# pc.net
KiCad netlist of a schematic drawn in EAGLE
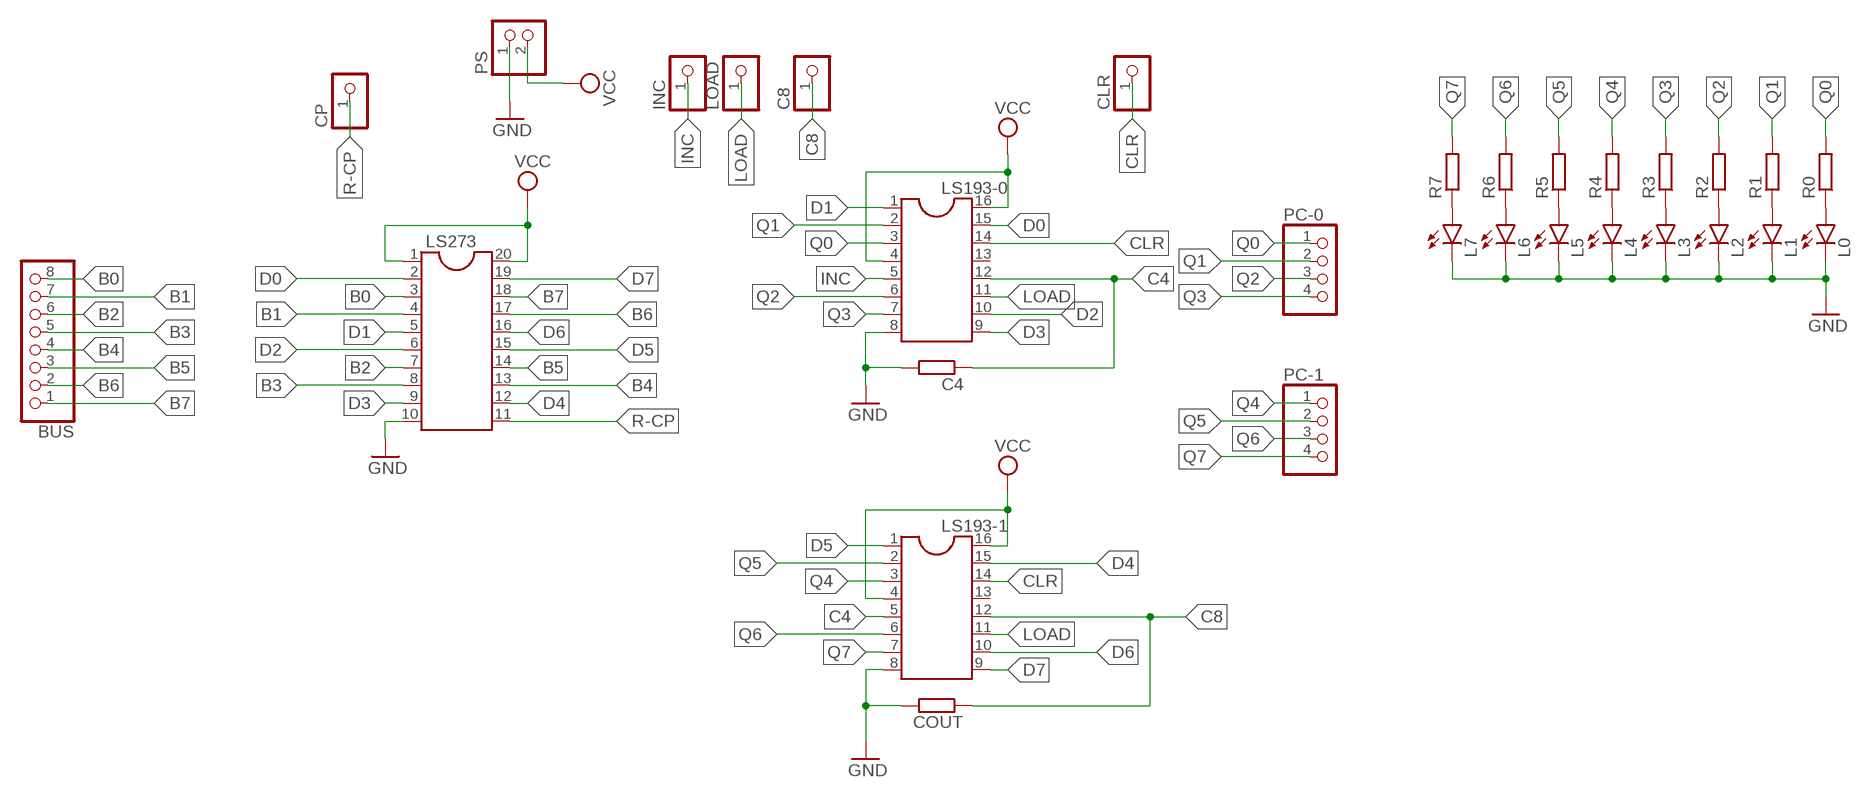
[diagram p0: schematic, sheet 1]

(export (version "E")
  (design (tool "Eeschema 10.0.6"))
  (components
    (comp (ref "BUS")
      (value "PINHD-1X8")
      (footprint "eagle-import:1X08")
      (libsource (lib "eagle-import") (part "PINHD-1X8"))
    )
    (comp (ref "C4")
      (value "R-EU_0204/7")
      (footprint "eagle-import:0204_7")
      (libsource (lib "eagle-import") (part "R-EU_0204/7"))
    )
    (comp (ref "C8")
      (value "PINHD-1X1")
      (footprint "eagle-import:1X01")
      (libsource (lib "eagle-import") (part "PINHD-1X1"))
    )
    (comp (ref "CLR")
      (value "PINHD-1X1")
      (footprint "eagle-import:1X01")
      (libsource (lib "eagle-import") (part "PINHD-1X1"))
    )
    (comp (ref "COUT")
      (value "R-EU_0204/7")
      (footprint "eagle-import:0204_7")
      (libsource (lib "eagle-import") (part "R-EU_0204/7"))
    )
    (comp (ref "CP")
      (value "PINHD-1X1")
      (footprint "eagle-import:1X01")
      (libsource (lib "eagle-import") (part "PINHD-1X1"))
    )
    (comp (ref "INC")
      (value "PINHD-1X1")
      (footprint "eagle-import:1X01")
      (libsource (lib "eagle-import") (part "PINHD-1X1"))
    )
    (comp (ref "L0")
      (value "LED5MM")
      (footprint "eagle-import:LED5MM")
      (libsource (lib "eagle-import") (part "LED5MM"))
    )
    (comp (ref "L1")
      (value "LED5MM")
      (footprint "eagle-import:LED5MM")
      (libsource (lib "eagle-import") (part "LED5MM"))
    )
    (comp (ref "L2")
      (value "LED5MM")
      (footprint "eagle-import:LED5MM")
      (libsource (lib "eagle-import") (part "LED5MM"))
    )
    (comp (ref "L3")
      (value "LED5MM")
      (footprint "eagle-import:LED5MM")
      (libsource (lib "eagle-import") (part "LED5MM"))
    )
    (comp (ref "L4")
      (value "LED5MM")
      (footprint "eagle-import:LED5MM")
      (libsource (lib "eagle-import") (part "LED5MM"))
    )
    (comp (ref "L5")
      (value "LED5MM")
      (footprint "eagle-import:LED5MM")
      (libsource (lib "eagle-import") (part "LED5MM"))
    )
    (comp (ref "L6")
      (value "LED5MM")
      (footprint "eagle-import:LED5MM")
      (libsource (lib "eagle-import") (part "LED5MM"))
    )
    (comp (ref "L7")
      (value "LED5MM")
      (footprint "eagle-import:LED5MM")
      (libsource (lib "eagle-import") (part "LED5MM"))
    )
    (comp (ref "LOAD")
      (value "PINHD-1X1")
      (footprint "eagle-import:1X01")
      (libsource (lib "eagle-import") (part "PINHD-1X1"))
    )
    (comp (ref "LS193-0")
      (value "DIL16S")
      (footprint "eagle-import:SOCKET-16")
      (libsource (lib "eagle-import") (part "DIL16S"))
    )
    (comp (ref "LS193-1")
      (value "DIL16S")
      (footprint "eagle-import:SOCKET-16")
      (libsource (lib "eagle-import") (part "DIL16S"))
    )
    (comp (ref "LS273")
      (value "DIL20S")
      (footprint "eagle-import:SOCKET-20")
      (libsource (lib "eagle-import") (part "DIL20S"))
    )
    (comp (ref "PC-0")
      (value "PINHD-1X4")
      (footprint "eagle-import:1X04")
      (libsource (lib "eagle-import") (part "PINHD-1X4"))
    )
    (comp (ref "PC-1")
      (value "PINHD-1X4")
      (footprint "eagle-import:1X04")
      (libsource (lib "eagle-import") (part "PINHD-1X4"))
    )
    (comp (ref "PS")
      (value "PINHD-1X2")
      (footprint "eagle-import:1X02")
      (libsource (lib "eagle-import") (part "PINHD-1X2"))
    )
    (comp (ref "R0")
      (value "R-EU_0204/7")
      (footprint "eagle-import:0204_7")
      (libsource (lib "eagle-import") (part "R-EU_0204/7"))
    )
    (comp (ref "R1")
      (value "R-EU_0204/7")
      (footprint "eagle-import:0204_7")
      (libsource (lib "eagle-import") (part "R-EU_0204/7"))
    )
    (comp (ref "R2")
      (value "R-EU_0204/7")
      (footprint "eagle-import:0204_7")
      (libsource (lib "eagle-import") (part "R-EU_0204/7"))
    )
    (comp (ref "R3")
      (value "R-EU_0204/7")
      (footprint "eagle-import:0204_7")
      (libsource (lib "eagle-import") (part "R-EU_0204/7"))
    )
    (comp (ref "R4")
      (value "R-EU_0204/7")
      (footprint "eagle-import:0204_7")
      (libsource (lib "eagle-import") (part "R-EU_0204/7"))
    )
    (comp (ref "R5")
      (value "R-EU_0204/7")
      (footprint "eagle-import:0204_7")
      (libsource (lib "eagle-import") (part "R-EU_0204/7"))
    )
    (comp (ref "R6")
      (value "R-EU_0204/7")
      (footprint "eagle-import:0204_7")
      (libsource (lib "eagle-import") (part "R-EU_0204/7"))
    )
    (comp (ref "R7")
      (value "R-EU_0204/7")
      (footprint "eagle-import:0204_7")
      (libsource (lib "eagle-import") (part "R-EU_0204/7"))
    )
  )
  (nets
    (net (code "1") (name "B0") (class "Default")
      (node (ref "BUS") (pin "8") (pinfunction "8_8") (pintype "passive"))
      (node (ref "LS273") (pin "3") (pinfunction "3_3") (pintype "passive"))
    )
    (net (code "2") (name "B1") (class "Default")
      (node (ref "BUS") (pin "7") (pinfunction "7_7") (pintype "passive"))
      (node (ref "LS273") (pin "4") (pinfunction "4_4") (pintype "passive"))
    )
    (net (code "3") (name "B2") (class "Default")
      (node (ref "BUS") (pin "6") (pinfunction "6_6") (pintype "passive"))
      (node (ref "LS273") (pin "7") (pinfunction "7_7") (pintype "passive"))
    )
    (net (code "4") (name "B3") (class "Default")
      (node (ref "BUS") (pin "5") (pinfunction "5_5") (pintype "passive"))
      (node (ref "LS273") (pin "8") (pinfunction "8_8") (pintype "passive"))
    )
    (net (code "5") (name "B4") (class "Default")
      (node (ref "BUS") (pin "4") (pinfunction "4_4") (pintype "passive"))
      (node (ref "LS273") (pin "13") (pinfunction "13_13") (pintype "passive"))
    )
    (net (code "6") (name "B5") (class "Default")
      (node (ref "BUS") (pin "3") (pinfunction "3_3") (pintype "passive"))
      (node (ref "LS273") (pin "14") (pinfunction "14_14") (pintype "passive"))
    )
    (net (code "7") (name "B6") (class "Default")
      (node (ref "BUS") (pin "2") (pinfunction "2_2") (pintype "passive"))
      (node (ref "LS273") (pin "17") (pinfunction "17_17") (pintype "passive"))
    )
    (net (code "8") (name "B7") (class "Default")
      (node (ref "BUS") (pin "1") (pinfunction "1_1") (pintype "passive"))
      (node (ref "LS273") (pin "18") (pinfunction "18_18") (pintype "passive"))
    )
    (net (code "9") (name "C4") (class "Default")
      (node (ref "C4") (pin "1") (pinfunction "1_1") (pintype "passive"))
      (node (ref "LS193-0") (pin "12") (pinfunction "12_12") (pintype "passive"))
      (node (ref "LS193-1") (pin "5") (pinfunction "5_5") (pintype "passive"))
    )
    (net (code "10") (name "C8") (class "Default")
      (node (ref "C8") (pin "1") (pinfunction "1_1") (pintype "passive"))
      (node (ref "COUT") (pin "1") (pinfunction "1_1") (pintype "passive"))
      (node (ref "LS193-1") (pin "12") (pinfunction "12_12") (pintype "passive"))
    )
    (net (code "11") (name "CLR") (class "Default")
      (node (ref "CLR") (pin "1") (pinfunction "1_1") (pintype "passive"))
      (node (ref "LS193-0") (pin "14") (pinfunction "14_14") (pintype "passive"))
      (node (ref "LS193-1") (pin "14") (pinfunction "14_14") (pintype "passive"))
    )
    (net (code "12") (name "D0") (class "Default")
      (node (ref "LS193-0") (pin "15") (pinfunction "15_15") (pintype "passive"))
      (node (ref "LS273") (pin "2") (pinfunction "2_2") (pintype "passive"))
    )
    (net (code "13") (name "D1") (class "Default")
      (node (ref "LS193-0") (pin "1") (pinfunction "1_1") (pintype "passive"))
      (node (ref "LS273") (pin "5") (pinfunction "5_5") (pintype "passive"))
    )
    (net (code "14") (name "D2") (class "Default")
      (node (ref "LS193-0") (pin "10") (pinfunction "10_10") (pintype "passive"))
      (node (ref "LS273") (pin "6") (pinfunction "6_6") (pintype "passive"))
    )
    (net (code "15") (name "D3") (class "Default")
      (node (ref "LS193-0") (pin "9") (pinfunction "9_9") (pintype "passive"))
      (node (ref "LS273") (pin "9") (pinfunction "9_9") (pintype "passive"))
    )
    (net (code "16") (name "D4") (class "Default")
      (node (ref "LS193-1") (pin "15") (pinfunction "15_15") (pintype "passive"))
      (node (ref "LS273") (pin "12") (pinfunction "12_12") (pintype "passive"))
    )
    (net (code "17") (name "D5") (class "Default")
      (node (ref "LS193-1") (pin "1") (pinfunction "1_1") (pintype "passive"))
      (node (ref "LS273") (pin "15") (pinfunction "15_15") (pintype "passive"))
    )
    (net (code "18") (name "D6") (class "Default")
      (node (ref "LS193-1") (pin "10") (pinfunction "10_10") (pintype "passive"))
      (node (ref "LS273") (pin "16") (pinfunction "16_16") (pintype "passive"))
    )
    (net (code "19") (name "D7") (class "Default")
      (node (ref "LS193-1") (pin "9") (pinfunction "9_9") (pintype "passive"))
      (node (ref "LS273") (pin "19") (pinfunction "19_19") (pintype "passive"))
    )
    (net (code "20") (name "GND") (class "Default")
      (node (ref "C4") (pin "2") (pinfunction "2_2") (pintype "passive"))
      (node (ref "COUT") (pin "2") (pinfunction "2_2") (pintype "passive"))
      (node (ref "L0") (pin "K") (pinfunction "C_K") (pintype "passive"))
      (node (ref "L1") (pin "K") (pinfunction "C_K") (pintype "passive"))
      (node (ref "L2") (pin "K") (pinfunction "C_K") (pintype "passive"))
      (node (ref "L3") (pin "K") (pinfunction "C_K") (pintype "passive"))
      (node (ref "L4") (pin "K") (pinfunction "C_K") (pintype "passive"))
      (node (ref "L5") (pin "K") (pinfunction "C_K") (pintype "passive"))
      (node (ref "L6") (pin "K") (pinfunction "C_K") (pintype "passive"))
      (node (ref "L7") (pin "K") (pinfunction "C_K") (pintype "passive"))
      (node (ref "LS193-0") (pin "8") (pinfunction "8_8") (pintype "passive"))
      (node (ref "LS193-1") (pin "8") (pinfunction "8_8") (pintype "passive"))
      (node (ref "LS273") (pin "10") (pinfunction "10_10") (pintype "passive"))
      (node (ref "PS") (pin "1") (pinfunction "1_1") (pintype "passive"))
    )
    (net (code "21") (name "INC") (class "Default")
      (node (ref "INC") (pin "1") (pinfunction "1_1") (pintype "passive"))
      (node (ref "LS193-0") (pin "5") (pinfunction "5_5") (pintype "passive"))
    )
    (net (code "22") (name "LOAD") (class "Default")
      (node (ref "LOAD") (pin "1") (pinfunction "1_1") (pintype "passive"))
      (node (ref "LS193-0") (pin "11") (pinfunction "11_11") (pintype "passive"))
      (node (ref "LS193-1") (pin "11") (pinfunction "11_11") (pintype "passive"))
    )
    (net (code "23") (name "Net-(L0-PadA)") (class "Default")
      (node (ref "L0") (pin "A") (pinfunction "A_A") (pintype "passive"))
      (node (ref "R0") (pin "1") (pinfunction "1_1") (pintype "passive"))
    )
    (net (code "24") (name "Net-(L1-PadA)") (class "Default")
      (node (ref "L1") (pin "A") (pinfunction "A_A") (pintype "passive"))
      (node (ref "R1") (pin "1") (pinfunction "1_1") (pintype "passive"))
    )
    (net (code "25") (name "Net-(L2-PadA)") (class "Default")
      (node (ref "L2") (pin "A") (pinfunction "A_A") (pintype "passive"))
      (node (ref "R2") (pin "1") (pinfunction "1_1") (pintype "passive"))
    )
    (net (code "26") (name "Net-(L3-PadA)") (class "Default")
      (node (ref "L3") (pin "A") (pinfunction "A_A") (pintype "passive"))
      (node (ref "R3") (pin "1") (pinfunction "1_1") (pintype "passive"))
    )
    (net (code "27") (name "Net-(L4-PadA)") (class "Default")
      (node (ref "L4") (pin "A") (pinfunction "A_A") (pintype "passive"))
      (node (ref "R4") (pin "1") (pinfunction "1_1") (pintype "passive"))
    )
    (net (code "28") (name "Net-(L5-PadA)") (class "Default")
      (node (ref "L5") (pin "A") (pinfunction "A_A") (pintype "passive"))
      (node (ref "R5") (pin "1") (pinfunction "1_1") (pintype "passive"))
    )
    (net (code "29") (name "Net-(L6-PadA)") (class "Default")
      (node (ref "L6") (pin "A") (pinfunction "A_A") (pintype "passive"))
      (node (ref "R6") (pin "1") (pinfunction "1_1") (pintype "passive"))
    )
    (net (code "30") (name "Net-(L7-PadA)") (class "Default")
      (node (ref "L7") (pin "A") (pinfunction "A_A") (pintype "passive"))
      (node (ref "R7") (pin "1") (pinfunction "1_1") (pintype "passive"))
    )
    (net (code "31") (name "Q0") (class "Default")
      (node (ref "LS193-0") (pin "3") (pinfunction "3_3") (pintype "passive"))
      (node (ref "PC-0") (pin "1") (pinfunction "1_1") (pintype "passive"))
      (node (ref "R0") (pin "2") (pinfunction "2_2") (pintype "passive"))
    )
    (net (code "32") (name "Q1") (class "Default")
      (node (ref "LS193-0") (pin "2") (pinfunction "2_2") (pintype "passive"))
      (node (ref "PC-0") (pin "2") (pinfunction "2_2") (pintype "passive"))
      (node (ref "R1") (pin "2") (pinfunction "2_2") (pintype "passive"))
    )
    (net (code "33") (name "Q2") (class "Default")
      (node (ref "LS193-0") (pin "6") (pinfunction "6_6") (pintype "passive"))
      (node (ref "PC-0") (pin "3") (pinfunction "3_3") (pintype "passive"))
      (node (ref "R2") (pin "2") (pinfunction "2_2") (pintype "passive"))
    )
    (net (code "34") (name "Q3") (class "Default")
      (node (ref "LS193-0") (pin "7") (pinfunction "7_7") (pintype "passive"))
      (node (ref "PC-0") (pin "4") (pinfunction "4_4") (pintype "passive"))
      (node (ref "R3") (pin "2") (pinfunction "2_2") (pintype "passive"))
    )
    (net (code "35") (name "Q4") (class "Default")
      (node (ref "LS193-1") (pin "3") (pinfunction "3_3") (pintype "passive"))
      (node (ref "PC-1") (pin "1") (pinfunction "1_1") (pintype "passive"))
      (node (ref "R4") (pin "2") (pinfunction "2_2") (pintype "passive"))
    )
    (net (code "36") (name "Q5") (class "Default")
      (node (ref "LS193-1") (pin "2") (pinfunction "2_2") (pintype "passive"))
      (node (ref "PC-1") (pin "2") (pinfunction "2_2") (pintype "passive"))
      (node (ref "R5") (pin "2") (pinfunction "2_2") (pintype "passive"))
    )
    (net (code "37") (name "Q6") (class "Default")
      (node (ref "LS193-1") (pin "6") (pinfunction "6_6") (pintype "passive"))
      (node (ref "PC-1") (pin "3") (pinfunction "3_3") (pintype "passive"))
      (node (ref "R6") (pin "2") (pinfunction "2_2") (pintype "passive"))
    )
    (net (code "38") (name "Q7") (class "Default")
      (node (ref "LS193-1") (pin "7") (pinfunction "7_7") (pintype "passive"))
      (node (ref "PC-1") (pin "4") (pinfunction "4_4") (pintype "passive"))
      (node (ref "R7") (pin "2") (pinfunction "2_2") (pintype "passive"))
    )
    (net (code "39") (name "R-CP") (class "Default")
      (node (ref "CP") (pin "1") (pinfunction "1_1") (pintype "passive"))
      (node (ref "LS273") (pin "11") (pinfunction "11_11") (pintype "passive"))
    )
    (net (code "40") (name "VCC") (class "Default")
      (node (ref "LS193-0") (pin "16") (pinfunction "16_16") (pintype "passive"))
      (node (ref "LS193-0") (pin "4") (pinfunction "4_4") (pintype "passive"))
      (node (ref "LS193-1") (pin "16") (pinfunction "16_16") (pintype "passive"))
      (node (ref "LS193-1") (pin "4") (pinfunction "4_4") (pintype "passive"))
      (node (ref "LS273") (pin "1") (pinfunction "1_1") (pintype "passive"))
      (node (ref "LS273") (pin "20") (pinfunction "20_20") (pintype "passive"))
      (node (ref "PS") (pin "2") (pinfunction "2_2") (pintype "passive"))
    )
    (net (code "41") (name "unconnected-(LS193-0-Pad13)") (class "Default")
      (node (ref "LS193-0") (pin "13") (pinfunction "13_13") (pintype "passive"))
    )
    (net (code "42") (name "unconnected-(LS193-1-Pad13)") (class "Default")
      (node (ref "LS193-1") (pin "13") (pinfunction "13_13") (pintype "passive"))
    )
  )
)
